# LED_Green_Direct_ActiveLow.net
KiCad netlist of a schematic drawn in Altium Designer
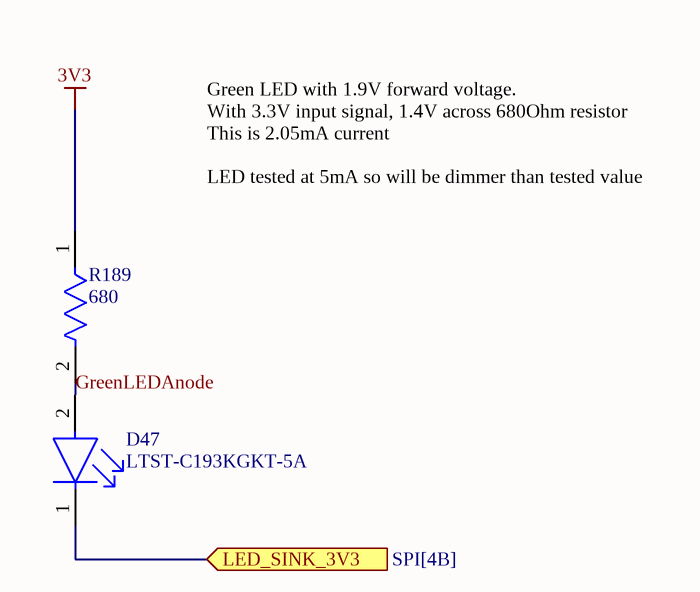
[diagram p0:  LED_Green_Direct_ActiveLow.SchDoc]

(export (version "E")
  (design (tool "Eeschema 10.0.6"))
  (components
    (comp (ref "D47")
      (value "LTST-C193KGKT-5A")
      (footprint "FP-LTST-C193KGKT-5A-MFG")
      (description "LED yellow green 0603 wavelength 567.5~576.5nm light intensity 4.5~28mcd Front Mounting")
      (libsource (lib "HIL RIG FYP") (part "8706943c75ba83719d021d2fdc84c58"))
    )
    (comp (ref "R189")
      (value "680")
      (footprint "FP-CRCW0603-e3-IPC_C")
      (description "Fixed Resistor, Metal Glaze/Thick Film, 0.1W, 680ohm, 75V, 5% +/-Tol, Surface Mount, 0603")
      (fields (field (name "TOLERANCE") "5%") (field (name "Comment") "CRCW0603680RJNEA"))
      (libsource (lib "HIL RIG FYP") (part "1029c3af85768c4190bb7ad29bc67b5"))
    )
  )
  (nets
    (net (code "1") (name "/GreenLEDAnode") (class "Default")
      (node (ref "D47") (pin "2") (pinfunction "A_2") (pintype "passive"))
      (node (ref "R189") (pin "2") (pinfunction "2_2") (pintype "passive"))
    )
    (net (code "2") (name "/LED_SINK_3V3") (class "Default")
      (node (ref "D47") (pin "1") (pinfunction "C_1") (pintype "passive"))
    )
    (net (code "3") (name "3V3") (class "Default")
      (node (ref "R189") (pin "1") (pinfunction "1_1") (pintype "passive"))
    )
  )
)
